# practicum_schematic.net
KiCad netlist of a schematic drawn in EAGLE
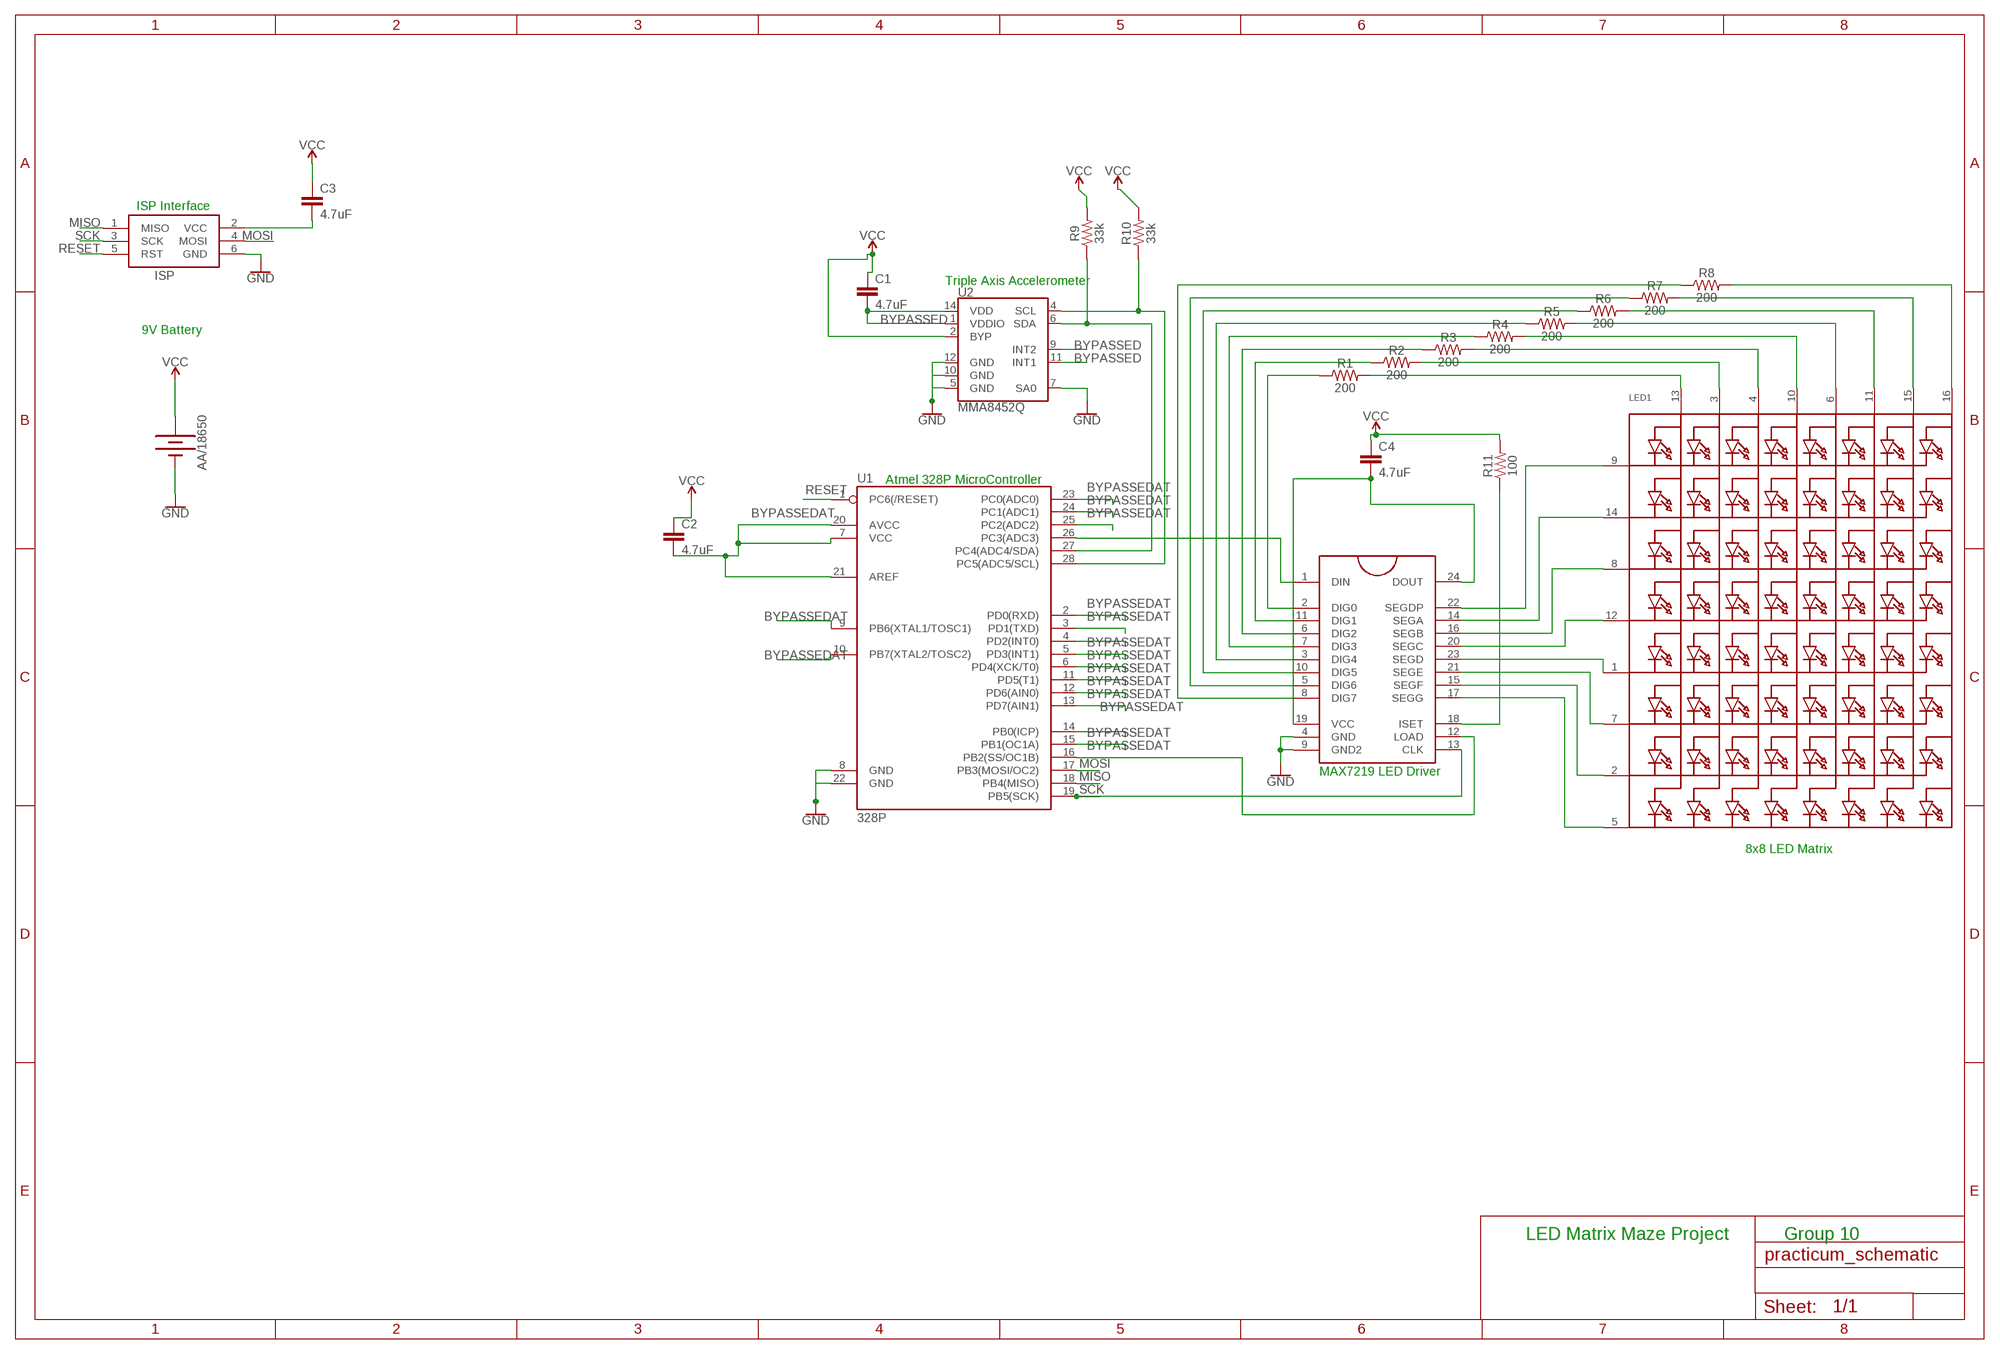
[diagram p0: schematic, sheet 1]

(export (version "E")
  (design (tool "Eeschema 10.0.6"))
  (components
    (comp (ref "AA/18650")
      (value "BATTERY-9V")
      (footprint "eagle-import:BATTCON_9V")
      (libsource (lib "eagle-import") (part "BATTERY-9V"))
    )
    (comp (ref "C1")
      (value "4.7uF")
      (footprint "eagle-import:0603")
      (libsource (lib "eagle-import") (part "4.7UF0603"))
    )
    (comp (ref "C2")
      (value "4.7uF")
      (footprint "eagle-import:0603")
      (libsource (lib "eagle-import") (part "4.7UF0603"))
    )
    (comp (ref "C3")
      (value "4.7uF")
      (footprint "eagle-import:0603")
      (libsource (lib "eagle-import") (part "4.7UF0603"))
    )
    (comp (ref "C4")
      (value "4.7uF")
      (footprint "eagle-import:0603")
      (libsource (lib "eagle-import") (part "4.7UF0603"))
    )
    (comp (ref "ISP")
      (value "AVRISP-6")
      (footprint "eagle-import:AVRISP")
      (libsource (lib "eagle-import") (part "AVRISP-6"))
    )
    (comp (ref "LED1")
      (value "SEGMENT_8X8_ROWCATHODEM12A881UR")
      (footprint "eagle-import:SEGMENT_BL-M12A881UR")
      (libsource (lib "eagle-import") (part "SEGMENT_8X8_ROWCATHODEM12A881UR"))
    )
    (comp (ref "R1")
      (value "200")
      (footprint "eagle-import:0603")
      (libsource (lib "eagle-import") (part "200OHM-0603-1/10W-1%"))
    )
    (comp (ref "R2")
      (value "200")
      (footprint "eagle-import:0603")
      (libsource (lib "eagle-import") (part "200OHM-0603-1/10W-1%"))
    )
    (comp (ref "R3")
      (value "200")
      (footprint "eagle-import:0603")
      (libsource (lib "eagle-import") (part "200OHM-0603-1/10W-1%"))
    )
    (comp (ref "R4")
      (value "200")
      (footprint "eagle-import:0603")
      (libsource (lib "eagle-import") (part "200OHM-0603-1/10W-1%"))
    )
    (comp (ref "R5")
      (value "200")
      (footprint "eagle-import:0603")
      (libsource (lib "eagle-import") (part "200OHM-0603-1/10W-1%"))
    )
    (comp (ref "R6")
      (value "200")
      (footprint "eagle-import:0603")
      (libsource (lib "eagle-import") (part "200OHM-0603-1/10W-1%"))
    )
    (comp (ref "R7")
      (value "200")
      (footprint "eagle-import:0603")
      (libsource (lib "eagle-import") (part "200OHM-0603-1/10W-1%"))
    )
    (comp (ref "R8")
      (value "200")
      (footprint "eagle-import:0603")
      (libsource (lib "eagle-import") (part "200OHM-0603-1/10W-1%"))
    )
    (comp (ref "R9")
      (value "33k")
      (footprint "eagle-import:0603")
      (libsource (lib "eagle-import") (part "33KOHM-0603-1/10W-1%"))
    )
    (comp (ref "R10")
      (value "33k")
      (footprint "eagle-import:0603")
      (libsource (lib "eagle-import") (part "33KOHM-0603-1/10W-1%"))
    )
    (comp (ref "R11")
      (value "100")
      (footprint "eagle-import:0603")
      (libsource (lib "eagle-import") (part "100OHM-0603-1/4W-5%"))
    )
    (comp (ref "U$1")
      (value "MAX7219DIP")
      (footprint "eagle-import:DIL24")
      (libsource (lib "eagle-import") (part "MAX7219DIP"))
    )
    (comp (ref "U1")
      (value "328P")
      (footprint "eagle-import:DIP28")
      (libsource (lib "eagle-import") (part "ATMEGA328P_PDIP"))
    )
    (comp (ref "U2")
      (value "MMA8452Q")
      (footprint "eagle-import:QFN-16")
      (libsource (lib "eagle-import") (part "MMA8452Q"))
    )
  )
  (nets
    (net (code "1") (name "/BYPASSED") (class "Default")
      (node (ref "C1") (pin "2") (pinfunction "2_2") (pintype "passive"))
      (node (ref "U2") (pin "1") (pinfunction "VDDIO_1") (pintype "bidirectional"))
      (node (ref "U2") (pin "11") (pinfunction "INT1_11") (pintype "bidirectional"))
      (node (ref "U2") (pin "14") (pinfunction "VDD_14") (pintype "bidirectional"))
      (node (ref "U2") (pin "9") (pinfunction "INT2_9") (pintype "bidirectional"))
    )
    (net (code "2") (name "/BYPASSEDAT") (class "Default")
      (node (ref "C2") (pin "2") (pinfunction "2_2") (pintype "passive"))
      (node (ref "U1") (pin "10") (pinfunction "PB7(XTAL2/TOSC2)_10") (pintype "bidirectional"))
      (node (ref "U1") (pin "11") (pinfunction "PD5(T1)_11") (pintype "bidirectional"))
      (node (ref "U1") (pin "12") (pinfunction "PD6(AIN0)_12") (pintype "bidirectional"))
      (node (ref "U1") (pin "13") (pinfunction "PD7(AIN1)_13") (pintype "bidirectional"))
      (node (ref "U1") (pin "14") (pinfunction "PB0(ICP)_14") (pintype "bidirectional"))
      (node (ref "U1") (pin "15") (pinfunction "PB1(OC1A)_15") (pintype "bidirectional"))
      (node (ref "U1") (pin "2") (pinfunction "PD0(RXD)_2") (pintype "bidirectional"))
      (node (ref "U1") (pin "20") (pinfunction "AVCC_20") (pintype "bidirectional"))
      (node (ref "U1") (pin "21") (pinfunction "AREF_21") (pintype "bidirectional"))
      (node (ref "U1") (pin "23") (pinfunction "PC0(ADC0)_23") (pintype "bidirectional"))
      (node (ref "U1") (pin "24") (pinfunction "PC1(ADC1)_24") (pintype "bidirectional"))
      (node (ref "U1") (pin "25") (pinfunction "PC2(ADC2)_25") (pintype "bidirectional"))
      (node (ref "U1") (pin "3") (pinfunction "PD1(TXD)_3") (pintype "bidirectional"))
      (node (ref "U1") (pin "4") (pinfunction "PD2(INT0)_4") (pintype "bidirectional"))
      (node (ref "U1") (pin "5") (pinfunction "PD3(INT1)_5") (pintype "bidirectional"))
      (node (ref "U1") (pin "6") (pinfunction "PD4(XCK/T0)_6") (pintype "bidirectional"))
      (node (ref "U1") (pin "7") (pinfunction "VCC_7") (pintype "bidirectional"))
      (node (ref "U1") (pin "9") (pinfunction "PB6(XTAL1/TOSC1)_9") (pintype "bidirectional"))
    )
    (net (code "3") (name "/MISO") (class "Default")
      (node (ref "ISP") (pin "1") (pinfunction "MISO_1") (pintype "input"))
      (node (ref "U1") (pin "18") (pinfunction "PB4(MISO)_18") (pintype "bidirectional"))
    )
    (net (code "4") (name "/MOSI") (class "Default")
      (node (ref "ISP") (pin "4") (pinfunction "MOSI_4") (pintype "output"))
      (node (ref "U1") (pin "17") (pinfunction "PB3(MOSI/OC2)_17") (pintype "bidirectional"))
    )
    (net (code "5") (name "/RESET") (class "Default")
      (node (ref "ISP") (pin "5") (pinfunction "RST_5") (pintype "output"))
      (node (ref "U1") (pin "1") (pinfunction "PC6(/RESET)_1") (pintype "bidirectional"))
    )
    (net (code "6") (name "/SCK") (class "Default")
      (node (ref "ISP") (pin "3") (pinfunction "SCK_3") (pintype "output"))
      (node (ref "U$1") (pin "13") (pinfunction "CLK_13") (pintype "bidirectional"))
      (node (ref "U1") (pin "19") (pinfunction "PB5(SCK)_19") (pintype "bidirectional"))
    )
    (net (code "7") (name "GND") (class "Default")
      (node (ref "AA/18650") (pin "-") (pinfunction "-_-") (pintype "power_in"))
      (node (ref "ISP") (pin "6") (pinfunction "GND_6") (pintype "power_in"))
      (node (ref "U$1") (pin "4") (pinfunction "GND_4") (pintype "bidirectional"))
      (node (ref "U$1") (pin "9") (pinfunction "GND2_9") (pintype "bidirectional"))
      (node (ref "U1") (pin "22") (pinfunction "GND_22") (pintype "bidirectional"))
      (node (ref "U1") (pin "8") (pinfunction "GND_8") (pintype "bidirectional"))
      (node (ref "U2") (pin "10") (pinfunction "GND_10") (pintype "bidirectional"))
      (node (ref "U2") (pin "12") (pinfunction "GND_12") (pintype "bidirectional"))
      (node (ref "U2") (pin "5") (pinfunction "GND_5") (pintype "bidirectional"))
      (node (ref "U2") (pin "7") (pinfunction "SA0_7") (pintype "bidirectional"))
    )
    (net (code "8") (name "Net-(ISP-VCC)") (class "Default")
      (node (ref "C3") (pin "2") (pinfunction "2_2") (pintype "passive"))
      (node (ref "ISP") (pin "2") (pinfunction "VCC_2") (pintype "power_in"))
    )
    (net (code "9") (name "Net-(LED1-A1)") (class "Default")
      (node (ref "LED1") (pin "13") (pinfunction "A1_13") (pintype "bidirectional"))
      (node (ref "R1") (pin "2") (pinfunction "2_2") (pintype "passive"))
    )
    (net (code "10") (name "Net-(LED1-A2)") (class "Default")
      (node (ref "LED1") (pin "3") (pinfunction "A2_3") (pintype "bidirectional"))
      (node (ref "R2") (pin "2") (pinfunction "2_2") (pintype "passive"))
    )
    (net (code "11") (name "Net-(LED1-A3)") (class "Default")
      (node (ref "LED1") (pin "4") (pinfunction "A3_4") (pintype "bidirectional"))
      (node (ref "R3") (pin "2") (pinfunction "2_2") (pintype "passive"))
    )
    (net (code "12") (name "Net-(LED1-A4)") (class "Default")
      (node (ref "LED1") (pin "10") (pinfunction "A4_10") (pintype "bidirectional"))
      (node (ref "R4") (pin "2") (pinfunction "2_2") (pintype "passive"))
    )
    (net (code "13") (name "Net-(LED1-A5)") (class "Default")
      (node (ref "LED1") (pin "6") (pinfunction "A5_6") (pintype "bidirectional"))
      (node (ref "R5") (pin "2") (pinfunction "2_2") (pintype "passive"))
    )
    (net (code "14") (name "Net-(LED1-A6)") (class "Default")
      (node (ref "LED1") (pin "11") (pinfunction "A6_11") (pintype "bidirectional"))
      (node (ref "R6") (pin "2") (pinfunction "2_2") (pintype "passive"))
    )
    (net (code "15") (name "Net-(LED1-A7)") (class "Default")
      (node (ref "LED1") (pin "15") (pinfunction "A7_15") (pintype "bidirectional"))
      (node (ref "R7") (pin "2") (pinfunction "2_2") (pintype "passive"))
    )
    (net (code "16") (name "Net-(LED1-A8)") (class "Default")
      (node (ref "LED1") (pin "16") (pinfunction "A8_16") (pintype "bidirectional"))
      (node (ref "R8") (pin "2") (pinfunction "2_2") (pintype "passive"))
    )
    (net (code "17") (name "Net-(LED1-K1)") (class "Default")
      (node (ref "LED1") (pin "9") (pinfunction "K1_9") (pintype "bidirectional"))
      (node (ref "U$1") (pin "22") (pinfunction "SEGDP_22") (pintype "bidirectional"))
    )
    (net (code "18") (name "Net-(LED1-K2)") (class "Default")
      (node (ref "LED1") (pin "14") (pinfunction "K2_14") (pintype "bidirectional"))
      (node (ref "U$1") (pin "14") (pinfunction "SEGA_14") (pintype "bidirectional"))
    )
    (net (code "19") (name "Net-(LED1-K3)") (class "Default")
      (node (ref "LED1") (pin "8") (pinfunction "K3_8") (pintype "bidirectional"))
      (node (ref "U$1") (pin "16") (pinfunction "SEGB_16") (pintype "bidirectional"))
    )
    (net (code "20") (name "Net-(LED1-K4)") (class "Default")
      (node (ref "LED1") (pin "12") (pinfunction "K4_12") (pintype "bidirectional"))
      (node (ref "U$1") (pin "20") (pinfunction "SEGC_20") (pintype "bidirectional"))
    )
    (net (code "21") (name "Net-(LED1-K5)") (class "Default")
      (node (ref "LED1") (pin "1") (pinfunction "K5_1") (pintype "bidirectional"))
      (node (ref "U$1") (pin "23") (pinfunction "SEGD_23") (pintype "bidirectional"))
    )
    (net (code "22") (name "Net-(LED1-K6)") (class "Default")
      (node (ref "LED1") (pin "7") (pinfunction "K6_7") (pintype "bidirectional"))
      (node (ref "U$1") (pin "21") (pinfunction "SEGE_21") (pintype "bidirectional"))
    )
    (net (code "23") (name "Net-(LED1-K7)") (class "Default")
      (node (ref "LED1") (pin "2") (pinfunction "K7_2") (pintype "bidirectional"))
      (node (ref "U$1") (pin "15") (pinfunction "SEGF_15") (pintype "bidirectional"))
    )
    (net (code "24") (name "Net-(LED1-K8)") (class "Default")
      (node (ref "LED1") (pin "5") (pinfunction "K8_5") (pintype "bidirectional"))
      (node (ref "U$1") (pin "17") (pinfunction "SEGG_17") (pintype "bidirectional"))
    )
    (net (code "25") (name "Net-(U$1-DIG0)") (class "Default")
      (node (ref "R1") (pin "1") (pinfunction "1_1") (pintype "passive"))
      (node (ref "U$1") (pin "2") (pinfunction "DIG0_2") (pintype "bidirectional"))
    )
    (net (code "26") (name "Net-(U$1-DIG1)") (class "Default")
      (node (ref "R2") (pin "1") (pinfunction "1_1") (pintype "passive"))
      (node (ref "U$1") (pin "11") (pinfunction "DIG1_11") (pintype "bidirectional"))
    )
    (net (code "27") (name "Net-(U$1-DIG2)") (class "Default")
      (node (ref "R3") (pin "1") (pinfunction "1_1") (pintype "passive"))
      (node (ref "U$1") (pin "6") (pinfunction "DIG2_6") (pintype "bidirectional"))
    )
    (net (code "28") (name "Net-(U$1-DIG3)") (class "Default")
      (node (ref "R4") (pin "1") (pinfunction "1_1") (pintype "passive"))
      (node (ref "U$1") (pin "7") (pinfunction "DIG3_7") (pintype "bidirectional"))
    )
    (net (code "29") (name "Net-(U$1-DIG4)") (class "Default")
      (node (ref "R5") (pin "1") (pinfunction "1_1") (pintype "passive"))
      (node (ref "U$1") (pin "3") (pinfunction "DIG4_3") (pintype "bidirectional"))
    )
    (net (code "30") (name "Net-(U$1-DIG5)") (class "Default")
      (node (ref "R6") (pin "1") (pinfunction "1_1") (pintype "passive"))
      (node (ref "U$1") (pin "10") (pinfunction "DIG5_10") (pintype "bidirectional"))
    )
    (net (code "31") (name "Net-(U$1-DIG6)") (class "Default")
      (node (ref "R7") (pin "1") (pinfunction "1_1") (pintype "passive"))
      (node (ref "U$1") (pin "5") (pinfunction "DIG6_5") (pintype "bidirectional"))
    )
    (net (code "32") (name "Net-(U$1-DIG7)") (class "Default")
      (node (ref "R8") (pin "1") (pinfunction "1_1") (pintype "passive"))
      (node (ref "U$1") (pin "8") (pinfunction "DIG7_8") (pintype "bidirectional"))
    )
    (net (code "33") (name "Net-(U$1-DIN)") (class "Default")
      (node (ref "U$1") (pin "1") (pinfunction "DIN_1") (pintype "bidirectional"))
      (node (ref "U1") (pin "26") (pinfunction "PC3(ADC3)_26") (pintype "bidirectional"))
    )
    (net (code "34") (name "Net-(U$1-DOUT)") (class "Default")
      (node (ref "C4") (pin "2") (pinfunction "2_2") (pintype "passive"))
      (node (ref "U$1") (pin "19") (pinfunction "VCC_19") (pintype "bidirectional"))
      (node (ref "U$1") (pin "24") (pinfunction "DOUT_24") (pintype "bidirectional"))
    )
    (net (code "35") (name "Net-(U$1-ISET)") (class "Default")
      (node (ref "R11") (pin "1") (pinfunction "1_1") (pintype "passive"))
      (node (ref "U$1") (pin "18") (pinfunction "ISET_18") (pintype "bidirectional"))
    )
    (net (code "36") (name "Net-(U$1-LOAD)") (class "Default")
      (node (ref "U$1") (pin "12") (pinfunction "LOAD_12") (pintype "bidirectional"))
      (node (ref "U1") (pin "16") (pinfunction "PB2(SS/OC1B)_16") (pintype "bidirectional"))
    )
    (net (code "37") (name "Net-(U1-PC4(ADC4{slash}SDA))") (class "Default")
      (node (ref "R9") (pin "1") (pinfunction "1_1") (pintype "passive"))
      (node (ref "U1") (pin "27") (pinfunction "PC4(ADC4/SDA)_27") (pintype "bidirectional"))
      (node (ref "U2") (pin "6") (pinfunction "SDA_6") (pintype "bidirectional"))
    )
    (net (code "38") (name "Net-(U1-PC5(ADC5{slash}SCL))") (class "Default")
      (node (ref "R10") (pin "1") (pinfunction "1_1") (pintype "passive"))
      (node (ref "U1") (pin "28") (pinfunction "PC5(ADC5/SCL)_28") (pintype "bidirectional"))
      (node (ref "U2") (pin "4") (pinfunction "SCL_4") (pintype "bidirectional"))
    )
    (net (code "39") (name "VCC") (class "Default")
      (node (ref "AA/18650") (pin "+") (pinfunction "+_+") (pintype "power_in"))
      (node (ref "C1") (pin "1") (pinfunction "1_1") (pintype "passive"))
      (node (ref "C2") (pin "1") (pinfunction "1_1") (pintype "passive"))
      (node (ref "C3") (pin "1") (pinfunction "1_1") (pintype "passive"))
      (node (ref "C4") (pin "1") (pinfunction "1_1") (pintype "passive"))
      (node (ref "R10") (pin "2") (pinfunction "2_2") (pintype "passive"))
      (node (ref "R11") (pin "2") (pinfunction "2_2") (pintype "passive"))
      (node (ref "R9") (pin "2") (pinfunction "2_2") (pintype "passive"))
      (node (ref "U2") (pin "2") (pinfunction "BYP_2") (pintype "bidirectional"))
    )
  )
)
